# Isolated_Bias.net
KiCad netlist of a schematic drawn in Altium Designer
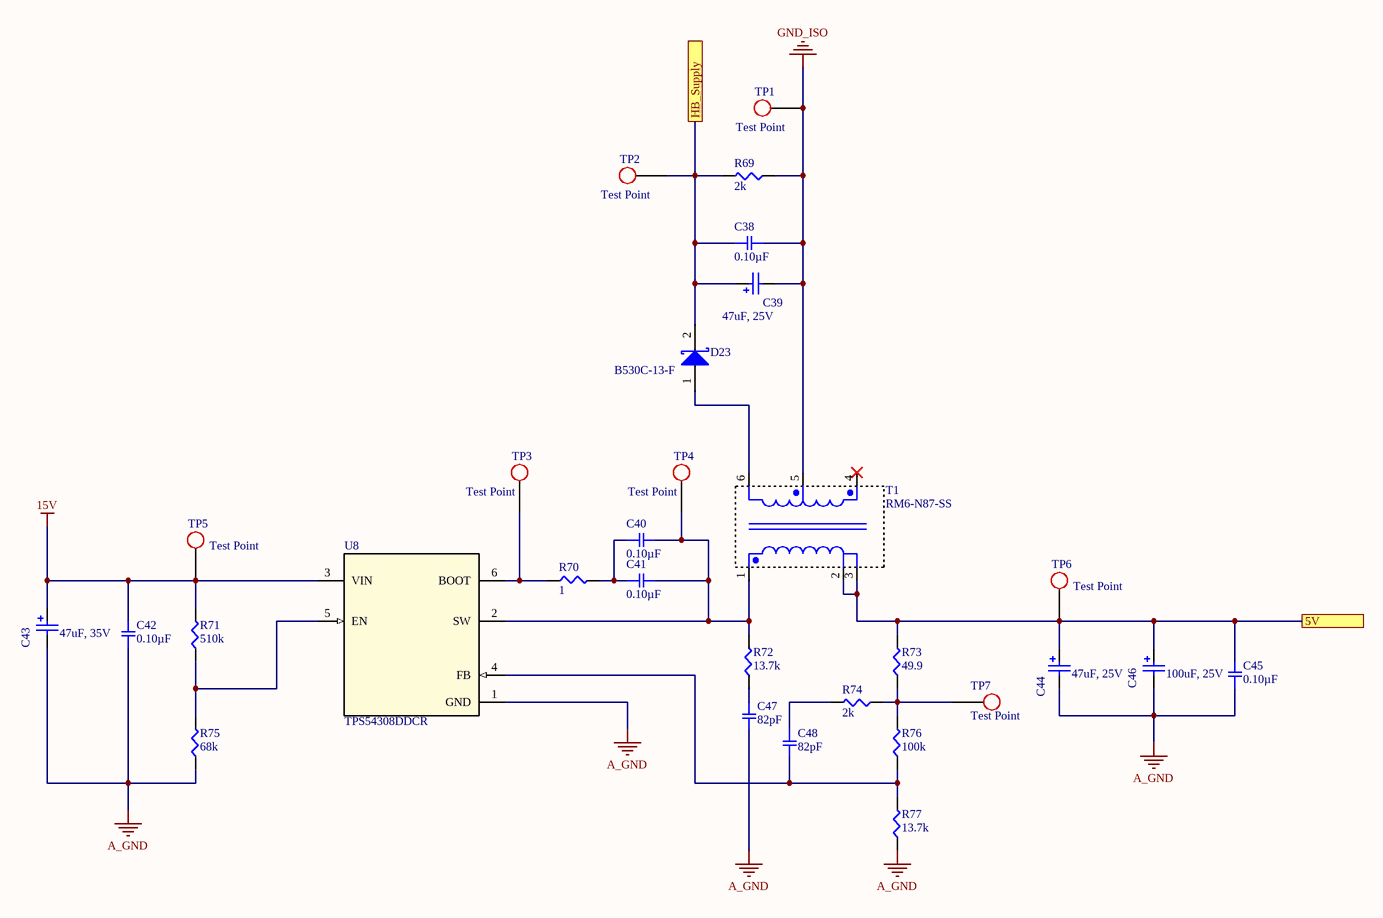
[diagram p0: Isolated_Bias.SchDoc]

(export (version "E")
  (design (tool "Eeschema 10.0.6"))
  (components
    (comp (ref "C38")
      (value "0.10µF")
      (footprint "SMD-0603C")
      (description "CAP CER 0.1UF 16V X7R 0603")
      (fields
        (field (name "DIGI-KEY PART NUMBER") "490-4774-1-ND")
        (field (name "PART NUMBER") "GCM188R71C104KA37D")
      )
      (libsource (lib "capacitor_murata_0603") (part "GCM188R71C104KA37D"))
    )
    (comp (ref "C39")
      (value "47uF, 25V")
      (footprint "WCAP-ASLL_6.3x5.5")
      (description "WCAP-ASLL SMT Aluminum Electrolytic Capacitors, D6.3mm x L5.5mm, 47uF, +/-20%, 25VDC")
      (fields (field (name "PART NUMBER") "865060443004") (field (name "PUBLISHER") "Wurth Elektronik"))
      (libsource (lib "Altium_WCAP-ASLL_SMD") (part "865060443004"))
    )
    (comp (ref "C40")
      (value "0.10µF")
      (footprint "SMD-0805C")
      (description "CAP CER 0.1UF 50V X7R 0805")
      (fields
        (field (name "DIGI-KEY PART NUMBER") "490-11955-1-ND")
        (field (name "PART NUMBER") "GCD21BR71H104KA01L")
      )
      (libsource (lib "capacitor_murata_0805") (part "GCD21BR71H104KA01L"))
    )
    (comp (ref "C41")
      (value "0.10µF")
      (footprint "SMD-0805C")
      (description "CAP CER 0.1UF 50V X7R 0805")
      (fields
        (field (name "DIGI-KEY PART NUMBER") "490-11955-1-ND")
        (field (name "PART NUMBER") "GCD21BR71H104KA01L")
      )
      (libsource (lib "capacitor_murata_0805") (part "GCD21BR71H104KA01L"))
    )
    (comp (ref "C42")
      (value "0.10µF")
      (footprint "SMD-0805C")
      (description "CAP CER 0.1UF 50V X7R 0805")
      (fields
        (field (name "DIGI-KEY PART NUMBER") "490-11955-1-ND")
        (field (name "PART NUMBER") "GCD21BR71H104KA01L")
      )
      (libsource (lib "capacitor_murata_0805") (part "GCD21BR71H104KA01L"))
    )
    (comp (ref "C43")
      (value "47uF, 35V")
      (footprint "WCAP-ASLL_6.3x5.5")
      (description "WCAP-ASLL SMT Aluminum Electrolytic Capacitors, D6.3mm x L5.5mm, 47uF, +/-20%, 35VDC")
      (fields (field (name "PART NUMBER") "865060543005") (field (name "PUBLISHER") "Wurth Elektronik"))
      (libsource (lib "Altium_WCAP-ASLL_SMD") (part "865060543005"))
    )
    (comp (ref "C44")
      (value "47uF, 25V")
      (footprint "WCAP-ASLL_6.3x5.5")
      (description "WCAP-ASLL SMT Aluminum Electrolytic Capacitors, D6.3mm x L5.5mm, 47uF, +/-20%, 25VDC")
      (fields (field (name "PART NUMBER") "865060443004") (field (name "PUBLISHER") "Wurth Elektronik"))
      (libsource (lib "Altium_WCAP-ASLL_SMD") (part "865060443004"))
    )
    (comp (ref "C45")
      (value "0.10µF")
      (footprint "SMD-0603C")
      (description "CAP CER 0.1UF 16V X7R 0603")
      (fields
        (field (name "DIGI-KEY PART NUMBER") "490-4774-1-ND")
        (field (name "PART NUMBER") "GCM188R71C104KA37D")
      )
      (libsource (lib "capacitor_murata_0603") (part "GCM188R71C104KA37D"))
    )
    (comp (ref "C46")
      (value "100uF, 25V")
      (footprint "WCAP-ASLU_8x6.5")
      (description "WCAP-ASLU Aluminium Electrolytic Capacitors, D8mm x L6.5mm, 100uF, +/-20%, 25VDC")
      (fields (field (name "PART NUMBER") "865090449009") (field (name "PUBLISHER") "Wurth Elektronik"))
      (libsource (lib "Altium_WCAP-ASLU_SMD") (part "865090449009"))
    )
    (comp (ref "C47")
      (value "82pF")
      (footprint "SMD-0805C")
      (description "CAP CER 82PF 50V NP0 0805")
      (fields
        (field (name "DIGI-KEY PART NUMBER") "490-3615-1-ND")
        (field (name "PART NUMBER") "GQM2195C1H820JB01D")
      )
      (libsource (lib "capacitor_murata_0805") (part "GQM2195C1H820JB01D"))
    )
    (comp (ref "C48")
      (value "82pF")
      (footprint "SMD-0805C")
      (description "CAP CER 82PF 50V NP0 0805")
      (fields
        (field (name "DIGI-KEY PART NUMBER") "490-3615-1-ND")
        (field (name "PART NUMBER") "GQM2195C1H820JB01D")
      )
      (libsource (lib "capacitor_murata_0805") (part "GQM2195C1H820JB01D"))
    )
    (comp (ref "D23")
      (value "B530C-13-F")
      (footprint "DIOD-SMC-2_V")
      (libsource (lib "Altium Content Vault") (part "DSKY-AK-2"))
    )
    (comp (ref "R69")
      (value "2k")
      (footprint "SMD-0603-RES")
      (description "RES SMD 2K OHM 1% 1/10W 0603")
      (fields
        (field (name "PART NUMBER") "ERJ-3EKF2001V")
        (field (name "DIGI-KEY PART NUMBER") "P2.00KHCT-ND")
      )
      (libsource (lib "Panasonic_ERJ_0603") (part "ERJ-3EKF2001V"))
    )
    (comp (ref "R70")
      (value "1")
      (footprint "SMD-0603-RES")
      (description "RES SMD 1 OHM 1% 1/4W 0603")
      (fields (field (name "PART NUMBER") "ERJ-3BQF1R0V") (field (name "DIGI-KEY PART NUMBER") "P17371CT-ND"))
      (libsource (lib "Panasonic_ERJ_0603") (part "ERJ-3BQF1R0V"))
    )
    (comp (ref "R71")
      (value "510k")
      (footprint "SMD-0603-RES")
      (description "RES SMD 510K OHM 1% 1/10W 0603")
      (fields
        (field (name "PART NUMBER") "ERJ-3EKF5103V")
        (field (name "DIGI-KEY PART NUMBER") "P510KHCT-ND")
      )
      (libsource (lib "Panasonic_ERJ_0603") (part "ERJ-3EKF5103V"))
    )
    (comp (ref "R72")
      (value "13.7k")
      (footprint "SMD-0603-RES")
      (description "RES SMD 13.7K OHM 1% 1/10W 0603")
      (fields
        (field (name "PART NUMBER") "ERJ-3EKF1372V")
        (field (name "DIGI-KEY PART NUMBER") "P13.7KHCT-ND")
      )
      (libsource (lib "Panasonic_ERJ_0603") (part "ERJ-3EKF1372V"))
    )
    (comp (ref "R73")
      (value "49.9")
      (footprint "SMD-0603-RES")
      (description "RES SMD 49.9 OHM 1% 1/10W 0603")
      (fields
        (field (name "PART NUMBER") "ERJ-3EKF49R9V")
        (field (name "DIGI-KEY PART NUMBER") "P49.9HCT-ND")
      )
      (libsource (lib "Panasonic_ERJ_0603") (part "ERJ-3EKF49R9V"))
    )
    (comp (ref "R74")
      (value "2k")
      (footprint "SMD-0603-RES")
      (description "RES SMD 2K OHM 1% 1/10W 0603")
      (fields
        (field (name "PART NUMBER") "ERJ-3EKF2001V")
        (field (name "DIGI-KEY PART NUMBER") "P2.00KHCT-ND")
      )
      (libsource (lib "Panasonic_ERJ_0603") (part "ERJ-3EKF2001V"))
    )
    (comp (ref "R75")
      (value "68k")
      (footprint "SMD-0603-RES")
      (description "RES SMD 68K OHM 1% 1/10W 0603")
      (fields
        (field (name "PART NUMBER") "ERJ-3EKF6802V")
        (field (name "DIGI-KEY PART NUMBER") "P68.0KHCT-ND")
      )
      (libsource (lib "Panasonic_ERJ_0603") (part "ERJ-3EKF6802V"))
    )
    (comp (ref "R76")
      (value "100k")
      (footprint "SMD-0603-RES")
      (description "RES SMD 100K OHM 5% 1/10W 0603")
      (fields
        (field (name "PART NUMBER") "ERJ-3GEYJ104V")
        (field (name "DIGI-KEY PART NUMBER") "P100KGCT-ND")
      )
      (libsource (lib "Panasonic_ERJ_0603") (part "ERJ-3GEYJ104V"))
    )
    (comp (ref "R77")
      (value "13.7k")
      (footprint "SMD-0603-RES")
      (description "RES SMD 13.7K OHM 1% 1/10W 0603")
      (fields
        (field (name "PART NUMBER") "ERJ-3EKF1372V")
        (field (name "DIGI-KEY PART NUMBER") "P13.7KHCT-ND")
      )
      (libsource (lib "Panasonic_ERJ_0603") (part "ERJ-3EKF1372V"))
    )
    (comp (ref "T1")
      (value "RM6-N87-SS")
      (footprint "RM6-N87-SS")
      (libsource (lib "Power Board UCC28951") (part "RM6-N87-SS"))
    )
    (comp (ref "TP1")
      (value "Test Point")
      (footprint "Test_point_THT")
      (libsource (lib "Power Board UCC28951") (part "Test Point"))
    )
    (comp (ref "TP2")
      (value "Test Point")
      (footprint "Test_point_THT")
      (libsource (lib "Power Board UCC28951") (part "Test Point"))
    )
    (comp (ref "TP3")
      (value "Test Point")
      (footprint "Test_point_THT")
      (libsource (lib "Power Board UCC28951") (part "Test Point"))
    )
    (comp (ref "TP4")
      (value "Test Point")
      (footprint "Test_point_THT")
      (libsource (lib "Power Board UCC28951") (part "Test Point"))
    )
    (comp (ref "TP5")
      (value "Test Point")
      (footprint "Test_point_THT")
      (libsource (lib "Power Board UCC28951") (part "Test Point"))
    )
    (comp (ref "TP6")
      (value "Test Point")
      (footprint "Test_point_THT")
      (libsource (lib "Power Board UCC28951") (part "Test Point"))
    )
    (comp (ref "TP7")
      (value "Test Point")
      (footprint "Test_point_THT")
      (libsource (lib "Power Board UCC28951") (part "Test Point"))
    )
    (comp (ref "U8")
      (value "TPS54308DDCR")
      (footprint "SOT95P278X110-6N")
      (description "Imported")
      (fields (field (name "MANUFACTURER") "Texas Instruments"))
      (libsource (lib "Power Board UCC28951") (part "TPS54308DDCR"))
    )
  )
  (nets
    (net (code "1") (name "/5V") (class "Default")
      (node (ref "C44") (pin "2") (pinfunction "P_2") (pintype "passive"))
      (node (ref "C45") (pin "2") (pinfunction "2_2") (pintype "passive"))
      (node (ref "C46") (pin "2") (pinfunction "P_2") (pintype "passive"))
      (node (ref "R73") (pin "2") (pinfunction "2_2") (pintype "passive"))
      (node (ref "T1") (pin "2") (pinfunction "2_2") (pintype "passive"))
      (node (ref "T1") (pin "3") (pinfunction "1_3") (pintype "passive"))
      (node (ref "TP6") (pin "1") (pinfunction "1_1") (pintype "passive"))
    )
    (net (code "2") (name "/HB_Supply") (class "Default")
      (node (ref "C38") (pin "1") (pinfunction "1_1") (pintype "passive"))
      (node (ref "C39") (pin "2") (pinfunction "P_2") (pintype "passive"))
      (node (ref "D23") (pin "2") (pinfunction "K_2") (pintype "passive"))
      (node (ref "R69") (pin "2") (pinfunction "2_2") (pintype "passive"))
      (node (ref "TP2") (pin "1") (pinfunction "1_1") (pintype "passive"))
    )
    (net (code "3") (name "15V") (class "Default")
      (node (ref "C42") (pin "2") (pinfunction "2_2") (pintype "passive"))
      (node (ref "C43") (pin "2") (pinfunction "P_2") (pintype "passive"))
      (node (ref "R71") (pin "2") (pinfunction "2_2") (pintype "passive"))
      (node (ref "TP5") (pin "1") (pinfunction "1_1") (pintype "passive"))
      (node (ref "U8") (pin "3") (pinfunction "VIN_3") (pintype "power_in"))
    )
    (net (code "4") (name "A_GND") (class "Default")
      (node (ref "C42") (pin "1") (pinfunction "1_1") (pintype "passive"))
      (node (ref "C43") (pin "1") (pinfunction "N_1") (pintype "passive"))
      (node (ref "C44") (pin "1") (pinfunction "N_1") (pintype "passive"))
      (node (ref "C45") (pin "1") (pinfunction "1_1") (pintype "passive"))
      (node (ref "C46") (pin "1") (pinfunction "N_1") (pintype "passive"))
      (node (ref "C47") (pin "2") (pinfunction "2_2") (pintype "passive"))
      (node (ref "R75") (pin "1") (pinfunction "1_1") (pintype "passive"))
      (node (ref "R77") (pin "1") (pinfunction "1_1") (pintype "passive"))
      (node (ref "U8") (pin "1") (pinfunction "GND_1") (pintype "power_in"))
    )
    (net (code "5") (name "GND_ISO") (class "Default")
      (node (ref "C38") (pin "2") (pinfunction "2_2") (pintype "passive"))
      (node (ref "C39") (pin "1") (pinfunction "N_1") (pintype "passive"))
      (node (ref "R69") (pin "1") (pinfunction "1_1") (pintype "passive"))
      (node (ref "T1") (pin "5") (pinfunction "5_5") (pintype "passive"))
      (node (ref "TP1") (pin "1") (pinfunction "1_1") (pintype "passive"))
    )
    (net (code "6") (name "Net-(C40-Pad1)") (class "Default")
      (node (ref "C40") (pin "1") (pinfunction "1_1") (pintype "passive"))
      (node (ref "C41") (pin "1") (pinfunction "1_1") (pintype "passive"))
      (node (ref "R70") (pin "2") (pinfunction "2_2") (pintype "passive"))
    )
    (net (code "7") (name "Net-(C47-Pad1)") (class "Default")
      (node (ref "C47") (pin "1") (pinfunction "1_1") (pintype "passive"))
      (node (ref "R72") (pin "1") (pinfunction "1_1") (pintype "passive"))
    )
    (net (code "8") (name "Net-(C48-Pad1)") (class "Default")
      (node (ref "C48") (pin "1") (pinfunction "1_1") (pintype "passive"))
      (node (ref "R74") (pin "2") (pinfunction "2_2") (pintype "passive"))
    )
    (net (code "9") (name "Net-(D23-A)") (class "Default")
      (node (ref "D23") (pin "1") (pinfunction "A_1") (pintype "passive"))
      (node (ref "T1") (pin "6") (pinfunction "6_6") (pintype "passive"))
    )
    (net (code "10") (name "Net-(R73-Pad1)") (class "Default")
      (node (ref "R73") (pin "1") (pinfunction "1_1") (pintype "passive"))
      (node (ref "R74") (pin "1") (pinfunction "1_1") (pintype "passive"))
      (node (ref "R76") (pin "2") (pinfunction "2_2") (pintype "passive"))
      (node (ref "TP7") (pin "1") (pinfunction "1_1") (pintype "passive"))
    )
    (net (code "11") (name "Net-(U8-BOOT)") (class "Default")
      (node (ref "R70") (pin "1") (pinfunction "1_1") (pintype "passive"))
      (node (ref "TP3") (pin "1") (pinfunction "1_1") (pintype "passive"))
      (node (ref "U8") (pin "6") (pinfunction "BOOT_6") (pintype "power_in"))
    )
    (net (code "12") (name "Net-(U8-EN)") (class "Default")
      (node (ref "R71") (pin "1") (pinfunction "1_1") (pintype "passive"))
      (node (ref "R75") (pin "2") (pinfunction "2_2") (pintype "passive"))
      (node (ref "U8") (pin "5") (pinfunction "EN_5") (pintype "input"))
    )
    (net (code "13") (name "Net-(U8-FB)") (class "Default")
      (node (ref "C48") (pin "2") (pinfunction "2_2") (pintype "passive"))
      (node (ref "R76") (pin "1") (pinfunction "1_1") (pintype "passive"))
      (node (ref "R77") (pin "2") (pinfunction "2_2") (pintype "passive"))
      (node (ref "U8") (pin "4") (pinfunction "FB_4") (pintype "input"))
    )
    (net (code "14") (name "Net-(U8-SW)") (class "Default")
      (node (ref "C40") (pin "2") (pinfunction "2_2") (pintype "passive"))
      (node (ref "C41") (pin "2") (pinfunction "2_2") (pintype "passive"))
      (node (ref "R72") (pin "2") (pinfunction "2_2") (pintype "passive"))
      (node (ref "T1") (pin "1") (pinfunction "1_1") (pintype "passive"))
      (node (ref "TP4") (pin "1") (pinfunction "1_1") (pintype "passive"))
      (node (ref "U8") (pin "2") (pinfunction "SW_2") (pintype "power_in"))
    )
    (net (code "15") (name "unconnected-(T1-Pad3)") (class "Default")
      (node (ref "T1") (pin "3") (pintype "passive"))
    )
    (net (code "16") (name "unconnected-(T1-Pad4)") (class "Default")
      (node (ref "T1") (pin "4") (pinfunction "4_4") (pintype "passive+no_connect"))
    )
    (net (code "17") (name "unconnected-(T1-Pad8)") (class "Default")
      (node (ref "T1") (pin "8") (pintype "passive"))
    )
  )
)
